# FU-AM-FU6861Q-B-002-HW-V3_0-20200620.net
KiCad netlist of a schematic drawn in Altium Designer
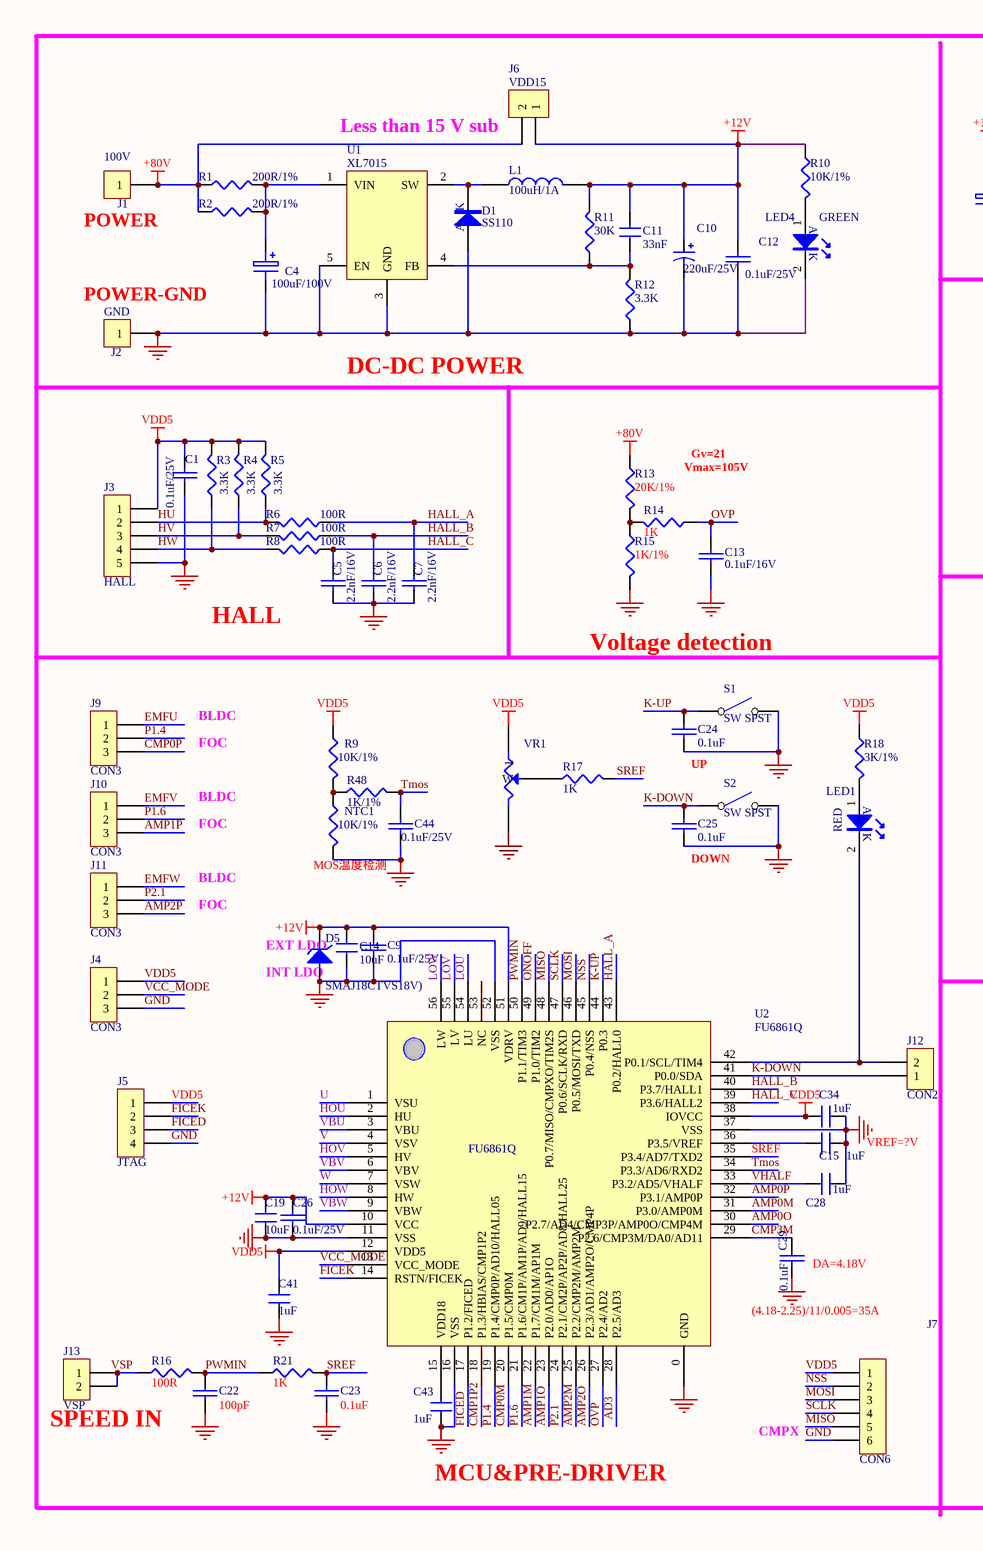
[diagram p0: FU-AM-FU6861Q-B-002-HW-V3.0-20200620.SchDoc, left]
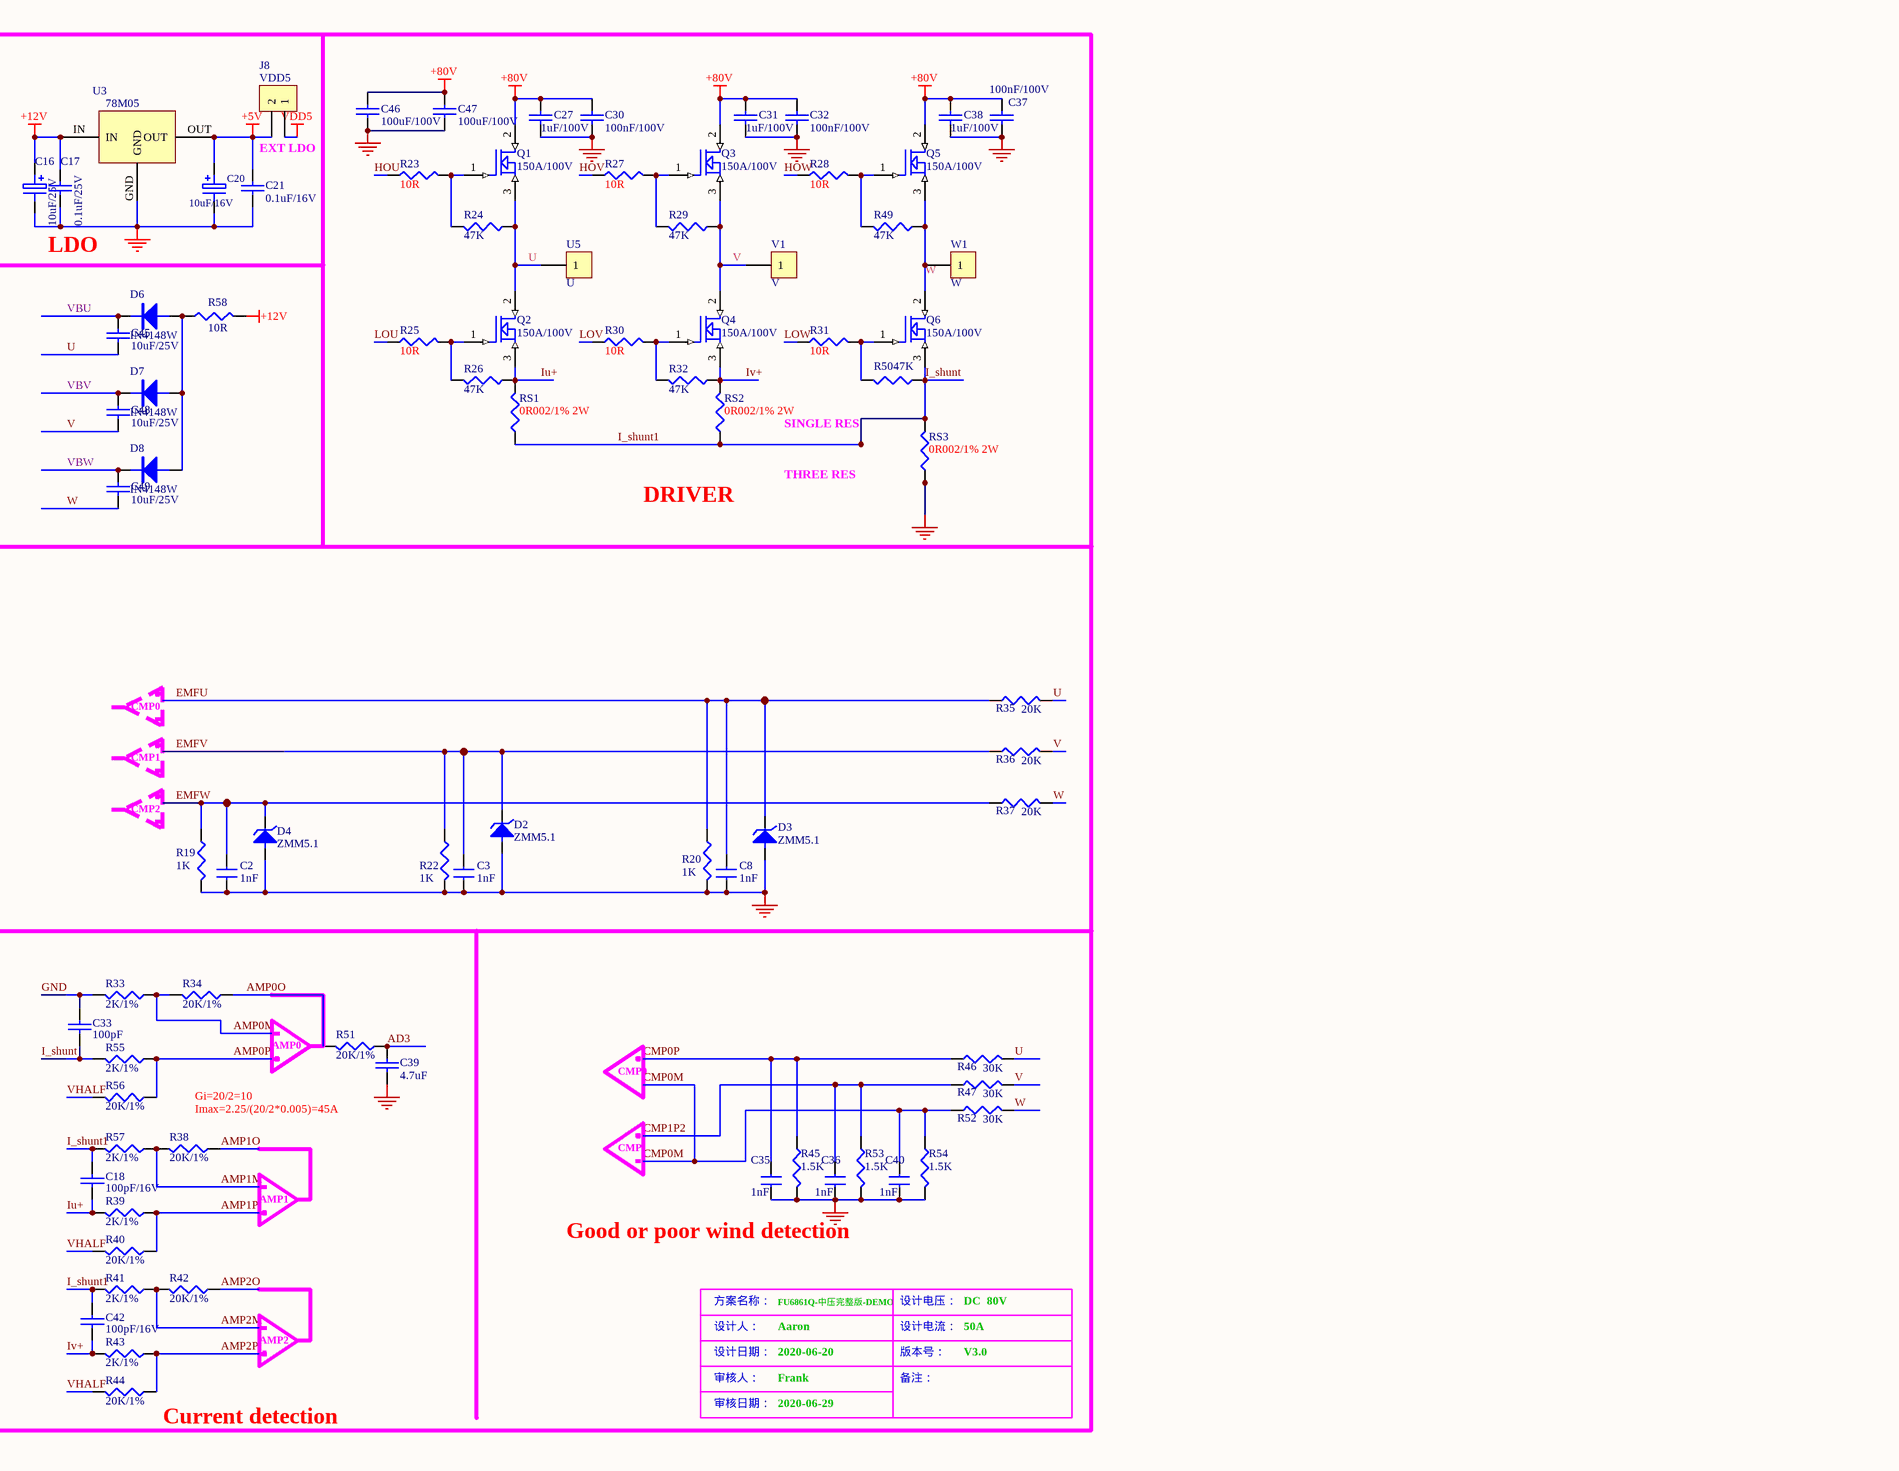
[diagram p1: FU-AM-FU6861Q-B-002-HW-V3.0-20200620.SchDoc, right]

(export (version "E")
  (design (tool "Eeschema 10.0.6"))
  (components
    (comp (ref "C1")
      (value "0.1uF/25V")
      (footprint "C0805")
      (description "Capacitor")
      (libsource (lib "") (part "CAP_1"))
    )
    (comp (ref "C2")
      (value "1nF")
      (footprint "C0805")
      (description "Capacitor")
      (libsource (lib "*") (part "CAP"))
    )
    (comp (ref "C3")
      (value "1nF")
      (footprint "C0805")
      (description "Capacitor")
      (libsource (lib "*") (part "CAP"))
    )
    (comp (ref "C4")
      (value "100uF/100V")
      (footprint "CE5-10/16")
      (description "Electrolytic Capacitor")
      (libsource (lib "*") (part "ELECTRO1"))
    )
    (comp (ref "C5")
      (value "2.2nF/16V")
      (footprint "C0805")
      (description "Capacitor")
      (libsource (lib "") (part "CAP_1"))
    )
    (comp (ref "C6")
      (value "2.2nF/16V")
      (footprint "C0805")
      (description "Capacitor")
      (libsource (lib "") (part "CAP_1"))
    )
    (comp (ref "C7")
      (value "2.2nF/16V")
      (footprint "C0805")
      (description "Capacitor")
      (libsource (lib "") (part "CAP_1"))
    )
    (comp (ref "C8")
      (value "1nF")
      (footprint "C0805")
      (description "Capacitor")
      (libsource (lib "*") (part "CAP"))
    )
    (comp (ref "C9")
      (value "0.1uF/25V")
      (footprint "C0805")
      (description "Capacitor")
      (libsource (lib "*") (part "CAP-CC"))
    )
    (comp (ref "C10")
      (value "220uF/25V")
      (footprint "CE3.5-8/12")
      (description "Polarized Capacitor (Radial)")
      (fields (field (name "PUBLISHER") "*"))
      (libsource (lib "*") (part "Cap Pol1"))
    )
    (comp (ref "C11")
      (value "33nF")
      (footprint "C0805")
      (description "Capacitor")
      (libsource (lib "*") (part "CAP"))
    )
    (comp (ref "C12")
      (value "0.1uF/25V")
      (footprint "C0805")
      (description "Capacitor")
      (libsource (lib "") (part "CAP_1"))
    )
    (comp (ref "C13")
      (value "0.1uF/16V")
      (footprint "C0805")
      (description "Capacitor")
      (libsource (lib "") (part "CAP_1"))
    )
    (comp (ref "C14")
      (value "10uF")
      (footprint "C0805")
      (description "Capacitor")
      (libsource (lib "*") (part "CAP"))
    )
    (comp (ref "C15")
      (value "1uF")
      (footprint "C0805")
      (description "Capacitor")
      (libsource (lib "*") (part "CAP"))
    )
    (comp (ref "C16")
      (value "10uF/25V")
      (footprint "C1206")
      (description "Electrolytic Capacitor")
      (libsource (lib "*") (part "ELECTRO1"))
    )
    (comp (ref "C17")
      (value "0.1uF/25V")
      (footprint "C0805")
      (description "Capacitor")
      (libsource (lib "") (part "CAP_1"))
    )
    (comp (ref "C18")
      (value "100pF/16V")
      (footprint "C0805")
      (description "Capacitor")
      (libsource (lib "") (part "CAP_1"))
    )
    (comp (ref "C19")
      (value "10uF")
      (footprint "C0805")
      (description "Capacitor")
      (libsource (lib "*") (part "CAP"))
    )
    (comp (ref "C20") (value "10uF/16V") (footprint "C1206") (libsource (lib "") (part "ELECTRO1_1")))
    (comp (ref "C21")
      (value "0.1uF/16V")
      (footprint "C0805")
      (description "Capacitor")
      (libsource (lib "*") (part "CAP-CC(SMD)"))
    )
    (comp (ref "C22")
      (value "100pF")
      (footprint "C0805")
      (description "Capacitor")
      (libsource (lib "*") (part "CAP-CC"))
    )
    (comp (ref "C23")
      (value "0.1uF")
      (footprint "C0805")
      (description "Capacitor")
      (libsource (lib "*") (part "CAP-CC"))
    )
    (comp (ref "C24")
      (value "0.1uF")
      (footprint "C0805")
      (description "Capacitor")
      (libsource (lib "") (part "CAP_1"))
    )
    (comp (ref "C25")
      (value "0.1uF")
      (footprint "C0805")
      (description "Capacitor")
      (libsource (lib "") (part "CAP_1"))
    )
    (comp (ref "C26")
      (value "0.1uF/25V")
      (footprint "C0805")
      (description "Capacitor")
      (libsource (lib "*") (part "CAP-CC"))
    )
    (comp (ref "C27")
      (value "1uF/100V")
      (footprint "C1206")
      (description "Capacitor")
      (libsource (lib "") (part "CAP_1"))
    )
    (comp (ref "C28")
      (value "1uF")
      (footprint "C0805")
      (description "Capacitor")
      (libsource (lib "*") (part "CAP"))
    )
    (comp (ref "C29")
      (value "0.1uF")
      (footprint "C0805")
      (description "Capacitor")
      (libsource (lib "") (part "CAP_1"))
    )
    (comp (ref "C30")
      (value "100nF/100V")
      (footprint "C1206")
      (description "Capacitor")
      (libsource (lib "") (part "CAP_1"))
    )
    (comp (ref "C31")
      (value "1uF/100V")
      (footprint "C1206")
      (description "Capacitor")
      (libsource (lib "") (part "CAP_1"))
    )
    (comp (ref "C32")
      (value "100nF/100V")
      (footprint "C1206")
      (description "Capacitor")
      (libsource (lib "") (part "CAP_1"))
    )
    (comp (ref "C33")
      (value "100pF")
      (footprint "C0805")
      (description "Capacitor")
      (libsource (lib "") (part "CAP_1"))
    )
    (comp (ref "C34")
      (value "1uF")
      (footprint "C0805")
      (description "Capacitor")
      (libsource (lib "*") (part "CAP"))
    )
    (comp (ref "C35")
      (value "1nF")
      (footprint "C0805")
      (description "Capacitor")
      (libsource (lib "*") (part "CAP"))
    )
    (comp (ref "C36")
      (value "1nF")
      (footprint "C0805")
      (description "Capacitor")
      (libsource (lib "*") (part "CAP"))
    )
    (comp (ref "C37")
      (value "100nF/100V")
      (footprint "C1206")
      (description "Capacitor")
      (libsource (lib "") (part "CAP_1"))
    )
    (comp (ref "C38")
      (value "1uF/100V")
      (footprint "C1206")
      (description "Capacitor")
      (libsource (lib "") (part "CAP_1"))
    )
    (comp (ref "C39")
      (value "4.7uF")
      (footprint "C0805")
      (description "Capacitor")
      (libsource (lib "") (part "CAP_1"))
    )
    (comp (ref "C40")
      (value "1nF")
      (footprint "C0805")
      (description "Capacitor")
      (libsource (lib "*") (part "CAP"))
    )
    (comp (ref "C41")
      (value "1uF")
      (footprint "C0805")
      (description "Capacitor")
      (libsource (lib "*") (part "CAP"))
    )
    (comp (ref "C42")
      (value "100pF/16V")
      (footprint "C0805")
      (description "Capacitor")
      (libsource (lib "") (part "CAP_1"))
    )
    (comp (ref "C43")
      (value "1uF")
      (footprint "C0805")
      (description "Capacitor")
      (libsource (lib "*") (part "CAP"))
    )
    (comp (ref "C44")
      (value "0.1uF/25V")
      (footprint "C0805")
      (description "Capacitor")
      (libsource (lib "*") (part "CAP-CC"))
    )
    (comp (ref "C45")
      (value "10uF/25V")
      (footprint "C0805")
      (description "Capacitor")
      (libsource (lib "*") (part "CAP-CC(SMD)"))
    )
    (comp (ref "C46")
      (value "100uF/100V")
      (footprint "CE7.5-16/25")
      (description "Capacitor")
      (libsource (lib "") (part "CAP_1"))
    )
    (comp (ref "C47")
      (value "100uF/100V")
      (footprint "CE7.5-16/25")
      (description "Capacitor")
      (libsource (lib "") (part "CAP_1"))
    )
    (comp (ref "C48")
      (value "10uF/25V")
      (footprint "C0805")
      (description "Capacitor")
      (libsource (lib "*") (part "CAP-CC(SMD)"))
    )
    (comp (ref "C49")
      (value "10uF/25V")
      (footprint "C0805")
      (description "Capacitor")
      (libsource (lib "*") (part "CAP-CC(SMD)"))
    )
    (comp (ref "D1")
      (value "SS110")
      (footprint "SMA")
      (description "Diode")
      (libsource (lib "*") (part "DIODE"))
    )
    (comp (ref "D2")
      (value "ZMM5.1")
      (footprint "SOD-123")
      (description "Zener Diode")
      (libsource (lib "*") (part "ZENER3"))
    )
    (comp (ref "D3")
      (value "ZMM5.1")
      (footprint "SOD-123")
      (description "Zener Diode")
      (libsource (lib "*") (part "ZENER3"))
    )
    (comp (ref "D4")
      (value "ZMM5.1")
      (footprint "SOD-123")
      (description "Zener Diode")
      (libsource (lib "*") (part "ZENER3"))
    )
    (comp (ref "D5")
      (value "SMAJ18CTVS18V)")
      (footprint "SMA")
      (description "Zener Diode")
      (libsource (lib "*") (part "TVS1"))
    )
    (comp (ref "D6")
      (value "IN4148W")
      (footprint "SOD-123")
      (description "Diode")
      (libsource (lib "*") (part "1N4004"))
    )
    (comp (ref "D7")
      (value "IN4148W")
      (footprint "SOD-123")
      (description "Diode")
      (libsource (lib "*") (part "1N4004"))
    )
    (comp (ref "D8")
      (value "IN4148W")
      (footprint "SOD-123")
      (description "Diode")
      (libsource (lib "*") (part "1N4004"))
    )
    (comp (ref "J1")
      (value "100V")
      (footprint "TP")
      (description "Connector")
      (libsource (lib "") (part "CON1_1"))
    )
    (comp (ref "J2")
      (value "GND")
      (footprint "TP")
      (description "Connector")
      (libsource (lib "") (part "CON1_1"))
    )
    (comp (ref "J3")
      (value "HALL")
      (footprint "XH-5P-2.54")
      (description "Connector")
      (libsource (lib "*") (part "CON5"))
    )
    (comp (ref "J4")
      (value "CON3")
      (footprint "SIP3-2.54")
      (description "Connector")
      (libsource (lib "*") (part "CON3"))
    )
    (comp (ref "J5")
      (value "JTAG")
      (footprint "SIP4-2.54")
      (description "Connector")
      (libsource (lib "*") (part "CON4"))
    )
    (comp (ref "J6")
      (value "VDD15")
      (footprint "SIP2-2.54")
      (description "Connector")
      (libsource (lib "*") (part "CON2"))
    )
    (comp (ref "J7")
      (value "CON6")
      (footprint "sip6-2.54")
      (description "Connector")
      (libsource (lib "*") (part "CON6"))
    )
    (comp (ref "J8")
      (value "VDD5")
      (footprint "SIP2-2.54")
      (description "Connector")
      (libsource (lib "*") (part "CON2"))
    )
    (comp (ref "J9")
      (value "CON3")
      (footprint "SIP3-2.54")
      (description "Connector")
      (libsource (lib "*") (part "CON3"))
    )
    (comp (ref "J10")
      (value "CON3")
      (footprint "SIP3-2.54")
      (description "Connector")
      (libsource (lib "*") (part "CON3"))
    )
    (comp (ref "J11")
      (value "CON3")
      (footprint "SIP3-2.54")
      (description "Connector")
      (libsource (lib "*") (part "CON3"))
    )
    (comp (ref "J12")
      (value "CON2")
      (footprint "SIP2-2.54")
      (description "Connector")
      (libsource (lib "SCH 常用封装") (part "CON2"))
    )
    (comp (ref "J13")
      (value "VSP")
      (footprint "SIP2-2.54")
      (description "Connector")
      (libsource (lib "") (part "CON2_1"))
    )
    (comp (ref "L1") (value "100uH/1A") (footprint "L4.5-9") (libsource (lib "*") (part "INDUCTOR")))
    (comp (ref "LED1") (value "RED") (footprint "LED0805") (libsource (lib "*") (part "LED")))
    (comp (ref "LED4") (value "GREEN") (footprint "LED0805") (libsource (lib "*") (part "LED")))
    (comp (ref "NTC1") (value "10K/1%") (footprint "R0805") (libsource (lib "*") (part "RES(SMD)")))
    (comp (ref "Q1")
      (value "150A/100V")
      (footprint "TO-220AB-W")
      (libsource (lib "*") (part "MOSFET N(GDS)"))
    )
    (comp (ref "Q2")
      (value "150A/100V")
      (footprint "TO-220AB-W")
      (libsource (lib "*") (part "MOSFET N(GDS)"))
    )
    (comp (ref "Q3")
      (value "150A/100V")
      (footprint "TO-220AB-W")
      (libsource (lib "*") (part "MOSFET N(GDS)"))
    )
    (comp (ref "Q4")
      (value "150A/100V")
      (footprint "TO-220AB-W")
      (libsource (lib "*") (part "MOSFET N(GDS)"))
    )
    (comp (ref "Q5")
      (value "150A/100V")
      (footprint "TO-220AB-W")
      (libsource (lib "*") (part "MOSFET N(GDS)"))
    )
    (comp (ref "Q6")
      (value "150A/100V")
      (footprint "TO-220AB-W")
      (libsource (lib "*") (part "MOSFET N(GDS)"))
    )
    (comp (ref "R1") (value "200R/1%") (footprint "R1206") (libsource (lib "*") (part "RES(SMD)")))
    (comp (ref "R2") (value "200R/1%") (footprint "R1206") (libsource (lib "*") (part "RES(SMD)")))
    (comp (ref "R3") (value "3.3K") (footprint "R0805") (libsource (lib "*") (part "RES(SMD)")))
    (comp (ref "R4") (value "3.3K") (footprint "R0805") (libsource (lib "*") (part "RES(SMD)")))
    (comp (ref "R5") (value "3.3K") (footprint "R0805") (libsource (lib "*") (part "RES(SMD)")))
    (comp (ref "R6") (value "100R") (footprint "R0805") (libsource (lib "*") (part "RES(SMD)")))
    (comp (ref "R7") (value "100R") (footprint "R0805") (libsource (lib "*") (part "RES(SMD)")))
    (comp (ref "R8") (value "100R") (footprint "R0805") (libsource (lib "*") (part "RES(SMD)")))
    (comp (ref "R9") (value "10K/1%") (footprint "R0805") (libsource (lib "*") (part "RES(SMD)")))
    (comp (ref "R10") (value "10K/1%") (footprint "R0805") (libsource (lib "*") (part "RES(SMD)")))
    (comp (ref "R11") (value "30K") (footprint "R0805") (libsource (lib "*") (part "RES(SMD)")))
    (comp (ref "R12") (value "3.3K") (footprint "R0805") (libsource (lib "*") (part "RES(SMD)")))
    (comp (ref "R13") (value "20K/1%") (footprint "R0805") (libsource (lib "*") (part "RES(SMD)")))
    (comp (ref "R14") (value "1K") (footprint "R0805") (libsource (lib "*") (part "RES(SMD)")))
    (comp (ref "R15") (value "1K/1%") (footprint "R0805") (libsource (lib "*") (part "RES(SMD)")))
    (comp (ref "R16") (value "100R") (footprint "R0805") (libsource (lib "*") (part "RES(SMD)")))
    (comp (ref "R17") (value "1K") (footprint "R0805") (libsource (lib "*") (part "RES(SMD)")))
    (comp (ref "R18") (value "3K/1%") (footprint "R0805") (libsource (lib "*") (part "RES(SMD)")))
    (comp (ref "R19")
      (value "1K")
      (footprint "R0805")
      (description "RES")
      (libsource (lib "*") (part "RES-SMD"))
    )
    (comp (ref "R20")
      (value "1K")
      (footprint "R0805")
      (description "RES")
      (libsource (lib "*") (part "RES-SMD"))
    )
    (comp (ref "R21") (value "1K") (footprint "R0805") (libsource (lib "*") (part "RES(SMD)")))
    (comp (ref "R22")
      (value "1K")
      (footprint "R0805")
      (description "RES")
      (libsource (lib "*") (part "RES-SMD"))
    )
    (comp (ref "R23") (value "10R") (footprint "R0805") (libsource (lib "*") (part "RES(SMD)")))
    (comp (ref "R24") (value "47K") (footprint "R0805") (libsource (lib "*") (part "RES(SMD)")))
    (comp (ref "R25") (value "10R") (footprint "R0805") (libsource (lib "*") (part "RES(SMD)")))
    (comp (ref "R26") (value "47K") (footprint "R0805") (libsource (lib "*") (part "RES(SMD)")))
    (comp (ref "R27") (value "10R") (footprint "R0805") (libsource (lib "*") (part "RES(SMD)")))
    (comp (ref "R28") (value "10R") (footprint "R0805") (libsource (lib "*") (part "RES(SMD)")))
    (comp (ref "R29") (value "47K") (footprint "R0805") (libsource (lib "*") (part "RES(SMD)")))
    (comp (ref "R30") (value "10R") (footprint "R0805") (libsource (lib "*") (part "RES(SMD)")))
    (comp (ref "R31") (value "10R") (footprint "R0805") (libsource (lib "*") (part "RES(SMD)")))
    (comp (ref "R32") (value "47K") (footprint "R0805") (libsource (lib "*") (part "RES(SMD)")))
    (comp (ref "R33") (value "2K/1%") (footprint "R0805") (libsource (lib "*") (part "RES(SMD)")))
    (comp (ref "R34") (value "20K/1%") (footprint "R0805") (libsource (lib "*") (part "RES(SMD)")))
    (comp (ref "R35")
      (value "20K")
      (footprint "R0805")
      (description "RES")
      (libsource (lib "*") (part "RES-SMD"))
    )
    (comp (ref "R36")
      (value "20K")
      (footprint "R0805")
      (description "RES")
      (libsource (lib "*") (part "RES-SMD"))
    )
    (comp (ref "R37")
      (value "20K")
      (footprint "R0805")
      (description "RES")
      (libsource (lib "*") (part "RES-SMD"))
    )
    (comp (ref "R38") (value "20K/1%") (footprint "R0805") (libsource (lib "*") (part "RES(SMD)")))
    (comp (ref "R39") (value "2K/1%") (footprint "R0805") (libsource (lib "*") (part "RES(SMD)")))
    (comp (ref "R40") (value "20K/1%") (footprint "R0805") (libsource (lib "*") (part "RES(SMD)")))
    (comp (ref "R41") (value "2K/1%") (footprint "R0805") (libsource (lib "*") (part "RES(SMD)")))
    (comp (ref "R42") (value "20K/1%") (footprint "R0805") (libsource (lib "*") (part "RES(SMD)")))
    (comp (ref "R43") (value "2K/1%") (footprint "R0805") (libsource (lib "*") (part "RES(SMD)")))
    (comp (ref "R44") (value "20K/1%") (footprint "R0805") (libsource (lib "*") (part "RES(SMD)")))
    (comp (ref "R45")
      (value "1.5K")
      (footprint "R0805")
      (description "RES")
      (libsource (lib "*") (part "RES-SMD"))
    )
    (comp (ref "R46")
      (value "30K")
      (footprint "R0805")
      (description "RES")
      (libsource (lib "*") (part "RES-SMD"))
    )
    (comp (ref "R47")
      (value "30K")
      (footprint "R0805")
      (description "RES")
      (libsource (lib "*") (part "RES-SMD"))
    )
    (comp (ref "R48") (value "1K/1%") (footprint "R0805") (libsource (lib "*") (part "RES(SMD)")))
    (comp (ref "R49") (value "47K") (footprint "R0805") (libsource (lib "*") (part "RES(SMD)")))
    (comp (ref "R50") (value "47K") (footprint "R0805") (libsource (lib "*") (part "RES(SMD)")))
    (comp (ref "R51") (value "20K/1%") (footprint "R0805") (libsource (lib "*") (part "RES(SMD)")))
    (comp (ref "R52")
      (value "30K")
      (footprint "R0805")
      (description "RES")
      (libsource (lib "*") (part "RES-SMD"))
    )
    (comp (ref "R53")
      (value "1.5K")
      (footprint "R0805")
      (description "RES")
      (libsource (lib "*") (part "RES-SMD"))
    )
    (comp (ref "R54")
      (value "1.5K")
      (footprint "R0805")
      (description "RES")
      (libsource (lib "*") (part "RES-SMD"))
    )
    (comp (ref "R55") (value "2K/1%") (footprint "R0805") (libsource (lib "*") (part "RES(SMD)")))
    (comp (ref "R56") (value "20K/1%") (footprint "R0805") (libsource (lib "*") (part "RES(SMD)")))
    (comp (ref "R57") (value "2K/1%") (footprint "R0805") (libsource (lib "*") (part "RES(SMD)")))
    (comp (ref "R58") (value "10R") (footprint "R1206") (libsource (lib "*") (part "RES(SMD)")))
    (comp (ref "RS1") (value "0R002/1% 2W") (footprint "R2512") (libsource (lib "*") (part "RES(SMD)")))
    (comp (ref "RS2") (value "0R002/1% 2W") (footprint "R2512") (libsource (lib "*") (part "RES(SMD)")))
    (comp (ref "RS3") (value "0R002/1% 2W") (footprint "R2512") (libsource (lib "*") (part "RES(SMD)")))
    (comp (ref "S1") (value "SW SPST") (footprint "SW-6/6") (libsource (lib "*") (part "SW SPST")))
    (comp (ref "S2") (value "SW SPST") (footprint "SW-6/6") (libsource (lib "*") (part "SW SPST")))
    (comp (ref "U1") (value "XL7015") (footprint "TO-252-5L") (libsource (lib "*") (part "XL7015")))
    (comp (ref "U2") (value "FU6861Q") (footprint "QFN56") (libsource (lib "*") (part "FU6861Q")))
    (comp (ref "U3") (value "78M05") (footprint "TO-252-3L") (libsource (lib "*") (part "78M05")))
    (comp (ref "U5")
      (value "U")
      (footprint "TP")
      (description "Connector")
      (libsource (lib "*") (part "CON1"))
    )
    (comp (ref "V1")
      (value "V")
      (footprint "TP")
      (description "Connector")
      (libsource (lib "*") (part "CON1"))
    )
    (comp (ref "VR1")
      (value "~")
      (footprint "VR6")
      (description "Potentiometer")
      (libsource (lib "*") (part "RV-3296"))
    )
    (comp (ref "W1")
      (value "W")
      (footprint "TP")
      (description "Connector")
      (libsource (lib "*") (part "CON1"))
    )
  )
  (nets
    (net (code "1") (name "+5V") (class "Default")
      (node (ref "C20") (pin "1") (pintype "passive"))
      (node (ref "C21") (pin "1") (pinfunction "1_1") (pintype "passive"))
      (node (ref "J8") (pin "2") (pinfunction "2_2") (pintype "passive"))
      (node (ref "U3") (pin "OUT") (pinfunction "OUT_OUT") (pintype "passive"))
    )
    (net (code "2") (name "+12V") (class "Default")
      (node (ref "C10") (pin "1") (pinfunction "1_1") (pintype "passive"))
      (node (ref "C11") (pin "1") (pinfunction "1_1") (pintype "passive"))
      (node (ref "C12") (pin "1") (pinfunction "1_1") (pintype "passive"))
      (node (ref "C14") (pin "2") (pinfunction "2_2") (pintype "passive"))
      (node (ref "C16") (pin "1") (pinfunction "1_1") (pintype "passive"))
      (node (ref "C17") (pin "1") (pinfunction "1_1") (pintype "passive"))
      (node (ref "C19") (pin "2") (pinfunction "2_2") (pintype "passive"))
      (node (ref "C26") (pin "1") (pinfunction "1_1") (pintype "passive"))
      (node (ref "C9") (pin "1") (pinfunction "1_1") (pintype "passive"))
      (node (ref "D5") (pin "2") (pinfunction "K_2") (pintype "passive"))
      (node (ref "J6") (pin "1") (pinfunction "1_1") (pintype "passive"))
      (node (ref "L1") (pin "2") (pinfunction "2_2") (pintype "passive"))
      (node (ref "R10") (pin "1") (pinfunction "1_1") (pintype "passive"))
      (node (ref "R11") (pin "2") (pinfunction "2_2") (pintype "passive"))
      (node (ref "R58") (pin "2") (pinfunction "2_2") (pintype "passive"))
      (node (ref "U2") (pin "10") (pinfunction "VCC_10") (pintype "passive"))
      (node (ref "U2") (pin "51") (pinfunction "VDRV_51") (pintype "passive"))
      (node (ref "U3") (pin "IN") (pinfunction "IN_IN") (pintype "passive"))
    )
    (net (code "3") (name "+80V") (class "Default")
      (node (ref "C27") (pin "1") (pinfunction "1_1") (pintype "passive"))
      (node (ref "C30") (pin "1") (pinfunction "1_1") (pintype "passive"))
      (node (ref "C31") (pin "1") (pinfunction "1_1") (pintype "passive"))
      (node (ref "C32") (pin "1") (pinfunction "1_1") (pintype "passive"))
      (node (ref "C37") (pin "1") (pinfunction "1_1") (pintype "passive"))
      (node (ref "C38") (pin "1") (pinfunction "1_1") (pintype "passive"))
      (node (ref "C46") (pin "1") (pinfunction "1_1") (pintype "passive"))
      (node (ref "C47") (pin "1") (pinfunction "1_1") (pintype "passive"))
      (node (ref "J1") (pin "1") (pinfunction "1_1") (pintype "passive"))
      (node (ref "J6") (pin "2") (pinfunction "2_2") (pintype "passive"))
      (node (ref "Q1") (pin "2") (pinfunction "D_2") (pintype "input"))
      (node (ref "Q3") (pin "2") (pinfunction "D_2") (pintype "input"))
      (node (ref "Q5") (pin "2") (pinfunction "D_2") (pintype "input"))
      (node (ref "R1") (pin "1") (pinfunction "1_1") (pintype "passive"))
      (node (ref "R13") (pin "1") (pinfunction "1_1") (pintype "passive"))
      (node (ref "R2") (pin "1") (pinfunction "1_1") (pintype "passive"))
    )
    (net (code "5") (name "/AD3") (class "Default")
      (node (ref "C39") (pin "1") (pinfunction "1_1") (pintype "passive"))
      (node (ref "R51") (pin "1") (pinfunction "1_1") (pintype "passive"))
      (node (ref "U2") (pin "28") (pinfunction "P2.5/AD3_28") (pintype "passive"))
    )
    (net (code "6") (name "/AMP0M") (class "Default")
      (node (ref "R33") (pin "1") (pinfunction "1_1") (pintype "passive"))
      (node (ref "R34") (pin "2") (pinfunction "2_2") (pintype "passive"))
      (node (ref "U2") (pin "31") (pinfunction "P3.0/AMP0M_31") (pintype "passive"))
    )
    (net (code "7") (name "/AMP0O") (class "Default")
      (node (ref "R34") (pin "1") (pinfunction "1_1") (pintype "passive"))
      (node (ref "R51") (pin "2") (pinfunction "2_2") (pintype "passive"))
      (node (ref "U2") (pin "30") (pinfunction "P2.7/AD4/CMP3P/AMP0O/CMP4M_30") (pintype "passive"))
    )
    (net (code "8") (name "/AMP0P") (class "Default")
      (node (ref "R55") (pin "1") (pinfunction "1_1") (pintype "passive"))
      (node (ref "R56") (pin "1") (pinfunction "1_1") (pintype "passive"))
      (node (ref "U2") (pin "32") (pinfunction "P3.1/AMP0P_32") (pintype "passive"))
    )
    (net (code "9") (name "/AMP1M") (class "Default")
      (node (ref "R38") (pin "2") (pinfunction "2_2") (pintype "passive"))
      (node (ref "R57") (pin "1") (pinfunction "1_1") (pintype "passive"))
      (node (ref "U2") (pin "22") (pinfunction "P1.7/CM1M/AP1M_22") (pintype "passive"))
    )
    (net (code "10") (name "/AMP1O") (class "Default")
      (node (ref "R38") (pin "1") (pinfunction "1_1") (pintype "passive"))
      (node (ref "U2") (pin "23") (pinfunction "P2.0/AD0/AP1O_23") (pintype "passive"))
    )
    (net (code "11") (name "/AMP1P") (class "Default")
      (node (ref "J10") (pin "3") (pinfunction "3_3") (pintype "passive"))
      (node (ref "R39") (pin "1") (pinfunction "1_1") (pintype "passive"))
      (node (ref "R40") (pin "1") (pinfunction "1_1") (pintype "passive"))
    )
    (net (code "12") (name "/AMP2M") (class "Default")
      (node (ref "R41") (pin "1") (pinfunction "1_1") (pintype "passive"))
      (node (ref "R42") (pin "2") (pinfunction "2_2") (pintype "passive"))
      (node (ref "U2") (pin "25") (pinfunction "P2.2/CMP2M/AMP2M_25") (pintype "passive"))
    )
    (net (code "13") (name "/AMP2O") (class "Default")
      (node (ref "R42") (pin "1") (pinfunction "1_1") (pintype "passive"))
      (node (ref "U2") (pin "26") (pinfunction "P2.3/AD1/AMP2O/CMP4P_26") (pintype "passive"))
    )
    (net (code "14") (name "/AMP2P") (class "Default")
      (node (ref "J11") (pin "3") (pinfunction "3_3") (pintype "passive"))
      (node (ref "R43") (pin "1") (pinfunction "1_1") (pintype "passive"))
      (node (ref "R44") (pin "1") (pinfunction "1_1") (pintype "passive"))
    )
    (net (code "15") (name "/CMP0M") (class "Default")
      (node (ref "C40") (pin "1") (pinfunction "1_1") (pintype "passive"))
      (node (ref "R52") (pin "1") (pinfunction "1_1") (pintype "passive"))
      (node (ref "R54") (pin "1") (pinfunction "1_1") (pintype "passive"))
      (node (ref "U2") (pin "20") (pinfunction "P1.5/CMP0M_20") (pintype "passive"))
    )
    (net (code "16") (name "/CMP0P") (class "Default")
      (node (ref "C35") (pin "1") (pinfunction "1_1") (pintype "passive"))
      (node (ref "J9") (pin "3") (pinfunction "3_3") (pintype "passive"))
      (node (ref "R45") (pin "1") (pinfunction "1_1") (pintype "passive"))
      (node (ref "R46") (pin "1") (pinfunction "1_1") (pintype "passive"))
    )
    (net (code "17") (name "/CMP1P2") (class "Default")
      (node (ref "C36") (pin "1") (pinfunction "1_1") (pintype "passive"))
      (node (ref "R47") (pin "1") (pinfunction "1_1") (pintype "passive"))
      (node (ref "R53") (pin "1") (pinfunction "1_1") (pintype "passive"))
      (node (ref "U2") (pin "18") (pinfunction "P1.3/HBIAS/CMP1P2_18") (pintype "passive"))
    )
    (net (code "18") (name "/CMP3M") (class "Default")
      (node (ref "C29") (pin "2") (pinfunction "2_2") (pintype "passive"))
      (node (ref "U2") (pin "29") (pinfunction "P2.6/CMP3M/DA0/AD11_29") (pintype "passive"))
    )
    (net (code "19") (name "/EMFU") (class "Default")
      (node (ref "C8") (pin "1") (pinfunction "1_1") (pintype "passive"))
      (node (ref "D3") (pin "2") (pinfunction "K_2") (pintype "passive"))
      (node (ref "J9") (pin "1") (pinfunction "1_1") (pintype "passive"))
      (node (ref "R20") (pin "1") (pinfunction "1_1") (pintype "passive"))
      (node (ref "R35") (pin "1") (pinfunction "1_1") (pintype "passive"))
    )
    (net (code "20") (name "/EMFV") (class "Default")
      (node (ref "C3") (pin "1") (pinfunction "1_1") (pintype "passive"))
      (node (ref "D2") (pin "2") (pinfunction "K_2") (pintype "passive"))
      (node (ref "J10") (pin "1") (pinfunction "1_1") (pintype "passive"))
      (node (ref "R22") (pin "1") (pinfunction "1_1") (pintype "passive"))
      (node (ref "R36") (pin "1") (pinfunction "1_1") (pintype "passive"))
    )
    (net (code "21") (name "/EMFW") (class "Default")
      (node (ref "C2") (pin "1") (pinfunction "1_1") (pintype "passive"))
      (node (ref "D4") (pin "2") (pinfunction "K_2") (pintype "passive"))
      (node (ref "J11") (pin "1") (pinfunction "1_1") (pintype "passive"))
      (node (ref "R19") (pin "1") (pinfunction "1_1") (pintype "passive"))
      (node (ref "R37") (pin "1") (pinfunction "1_1") (pintype "passive"))
    )
    (net (code "22") (name "/FICED") (class "Default")
      (node (ref "J5") (pin "3") (pinfunction "3_3") (pintype "passive"))
      (node (ref "U2") (pin "17") (pinfunction "P1.2/FICED_17") (pintype "passive"))
    )
    (net (code "23") (name "/FICEK") (class "Default")
      (node (ref "J5") (pin "2") (pinfunction "2_2") (pintype "passive"))
      (node (ref "U2") (pin "14") (pinfunction "RSTN/FICEK_14") (pintype "passive"))
    )
    (net (code "24") (name "/HALL_A") (class "Default")
      (node (ref "C7") (pin "2") (pinfunction "2_2") (pintype "passive"))
      (node (ref "R6") (pin "1") (pinfunction "1_1") (pintype "passive"))
      (node (ref "U2") (pin "43") (pinfunction "P0.2/HALL0_43") (pintype "passive"))
    )
    (net (code "25") (name "/HALL_B") (class "Default")
      (node (ref "C6") (pin "2") (pinfunction "2_2") (pintype "passive"))
      (node (ref "R7") (pin "1") (pinfunction "1_1") (pintype "passive"))
      (node (ref "U2") (pin "40") (pinfunction "P3.7/HALL1_40") (pintype "passive"))
    )
    (net (code "26") (name "/HALL_C") (class "Default")
      (node (ref "C5") (pin "2") (pinfunction "2_2") (pintype "passive"))
      (node (ref "R8") (pin "1") (pinfunction "1_1") (pintype "passive"))
      (node (ref "U2") (pin "39") (pinfunction "P3.6/HALL2_39") (pintype "passive"))
    )
    (net (code "27") (name "/HOU") (class "Default")
      (node (ref "R23") (pin "1") (pinfunction "1_1") (pintype "passive"))
      (node (ref "U2") (pin "2") (pinfunction "HU_2") (pintype "passive"))
    )
    (net (code "28") (name "/HOV") (class "Default")
      (node (ref "R27") (pin "1") (pinfunction "1_1") (pintype "passive"))
      (node (ref "U2") (pin "5") (pinfunction "HV_5") (pintype "passive"))
    )
    (net (code "29") (name "/HOW") (class "Default")
      (node (ref "R28") (pin "1") (pinfunction "1_1") (pintype "passive"))
      (node (ref "U2") (pin "8") (pinfunction "HW_8") (pintype "passive"))
    )
    (net (code "30") (name "/HU") (class "Default")
      (node (ref "J3") (pin "2") (pinfunction "2_2") (pintype "passive"))
      (node (ref "R5") (pin "1") (pinfunction "1_1") (pintype "passive"))
      (node (ref "R6") (pin "2") (pinfunction "2_2") (pintype "passive"))
    )
    (net (code "31") (name "/HV") (class "Default")
      (node (ref "J3") (pin "3") (pinfunction "3_3") (pintype "passive"))
      (node (ref "R4") (pin "1") (pinfunction "1_1") (pintype "passive"))
      (node (ref "R7") (pin "2") (pinfunction "2_2") (pintype "passive"))
    )
    (net (code "32") (name "/HW") (class "Default")
      (node (ref "J3") (pin "4") (pinfunction "4_4") (pintype "passive"))
      (node (ref "R3") (pin "1") (pinfunction "1_1") (pintype "passive"))
      (node (ref "R8") (pin "2") (pinfunction "2_2") (pintype "passive"))
    )
    (net (code "33") (name "/I_shunt") (class "Default")
      (node (ref "C18") (pin "1") (pinfunction "1_1") (pintype "passive"))
      (node (ref "C33") (pin "2") (pinfunction "2_2") (pintype "passive"))
      (node (ref "C42") (pin "1") (pinfunction "1_1") (pintype "passive"))
      (node (ref "Q6") (pin "3") (pinfunction "S_3") (pintype "input"))
      (node (ref "R41") (pin "2") (pinfunction "2_2") (pintype "passive"))
      (node (ref "R50") (pin "1") (pinfunction "1_1") (pintype "passive"))
      (node (ref "R55") (pin "2") (pinfunction "2_2") (pintype "passive"))
      (node (ref "R57") (pin "2") (pinfunction "2_2") (pintype "passive"))
      (node (ref "RS1") (pin "1") (pinfunction "1_1") (pintype "passive"))
      (node (ref "RS2") (pin "1") (pinfunction "1_1") (pintype "passive"))
      (node (ref "RS3") (pin "2") (pinfunction "2_2") (pintype "passive"))
    )
    (net (code "34") (name "/Iu+") (class "Default")
      (node (ref "C18") (pin "2") (pinfunction "2_2") (pintype "passive"))
      (node (ref "Q2") (pin "3") (pinfunction "S_3") (pintype "input"))
      (node (ref "R26") (pin "1") (pinfunction "1_1") (pintype "passive"))
      (node (ref "R39") (pin "2") (pinfunction "2_2") (pintype "passive"))
      (node (ref "RS1") (pin "2") (pinfunction "2_2") (pintype "passive"))
    )
    (net (code "35") (name "/Iv+") (class "Default")
      (node (ref "C42") (pin "2") (pinfunction "2_2") (pintype "passive"))
      (node (ref "Q4") (pin "3") (pinfunction "S_3") (pintype "input"))
      (node (ref "R32") (pin "1") (pinfunction "1_1") (pintype "passive"))
      (node (ref "R43") (pin "2") (pinfunction "2_2") (pintype "passive"))
      (node (ref "RS2") (pin "2") (pinfunction "2_2") (pintype "passive"))
    )
    (net (code "36") (name "/K-DOWN") (class "Default")
      (node (ref "C25") (pin "1") (pinfunction "1_1") (pintype "passive"))
      (node (ref "J12") (pin "1") (pinfunction "1_1") (pintype "passive"))
      (node (ref "S2") (pin "1") (pinfunction "COMMON_1") (pintype "passive"))
      (node (ref "U2") (pin "41") (pinfunction "P0.0/SDA_41") (pintype "passive"))
    )
    (net (code "37") (name "/K-UP") (class "Default")
      (node (ref "C24") (pin "1") (pinfunction "1_1") (pintype "passive"))
      (node (ref "S1") (pin "1") (pinfunction "COMMON_1") (pintype "passive"))
      (node (ref "U2") (pin "44") (pinfunction "P0.3_44") (pintype "passive"))
    )
    (net (code "38") (name "/LOU") (class "Default")
      (node (ref "R25") (pin "1") (pinfunction "1_1") (pintype "passive"))
      (node (ref "U2") (pin "54") (pinfunction "LU_54") (pintype "passive"))
    )
    (net (code "39") (name "/LOV") (class "Default")
      (node (ref "R30") (pin "1") (pinfunction "1_1") (pintype "passive"))
      (node (ref "U2") (pin "55") (pinfunction "LV_55") (pintype "passive"))
    )
    (net (code "40") (name "/LOW") (class "Default")
      (node (ref "R31") (pin "1") (pinfunction "1_1") (pintype "passive"))
      (node (ref "U2") (pin "56") (pinfunction "LW_56") (pintype "passive"))
    )
    (net (code "41") (name "/MISO") (class "Default")
      (node (ref "J7") (pin "5") (pinfunction "5_5") (pintype "passive"))
      (node (ref "U2") (pin "48") (pinfunction "P0.7/MISO/CMPXO/TIM2S_48") (pintype "passive"))
    )
    (net (code "42") (name "/MOSI") (class "Default")
      (node (ref "J7") (pin "3") (pinfunction "3_3") (pintype "passive"))
      (node (ref "U2") (pin "46") (pinfunction "P0.5/MOSI/TXD_46") (pintype "passive"))
    )
    (net (code "43") (name "/NSS") (class "Default")
      (node (ref "J7") (pin "2") (pinfunction "2_2") (pintype "passive"))
      (node (ref "U2") (pin "45") (pinfunction "P0.4/NSS_45") (pintype "passive"))
    )
    (net (code "44") (name "/ONOFF") (class "Default")
      (node (ref "U2") (pin "49") (pinfunction "P1.0/TIM2_49") (pintype "passive"))
    )
    (net (code "45") (name "/OVP") (class "Default")
      (node (ref "C13") (pin "1") (pinfunction "1_1") (pintype "passive"))
      (node (ref "R14") (pin "1") (pinfunction "1_1") (pintype "passive"))
      (node (ref "U2") (pin "27") (pinfunction "P2.4/AD2_27") (pintype "passive"))
    )
    (net (code "46") (name "/P1.4") (class "Default")
      (node (ref "J9") (pin "2") (pinfunction "2_2") (pintype "passive"))
      (node (ref "U2") (pin "19") (pinfunction "P1.4/CMP0P/AD10/HALL05_19") (pintype "passive"))
    )
    (net (code "47") (name "/P1.6") (class "Default")
      (node (ref "J10") (pin "2") (pinfunction "2_2") (pintype "passive"))
      (node (ref "U2") (pin "21") (pinfunction "P1.6/CM1P/AM1P/AD9/HALL15_21") (pintype "passive"))
    )
    (net (code "48") (name "/P2.1") (class "Default")
      (node (ref "J11") (pin "2") (pinfunction "2_2") (pintype "passive"))
      (node (ref "U2") (pin "24") (pinfunction "P2.1/CM2P/AP2P/AD8/HALL25_24") (pintype "passive"))
    )
    (net (code "49") (name "/PWMIN") (class "Default")
      (node (ref "C22") (pin "1") (pinfunction "1_1") (pintype "passive"))
      (node (ref "R16") (pin "2") (pinfunction "2_2") (pintype "passive"))
      (node (ref "R21") (pin "1") (pinfunction "1_1") (pintype "passive"))
      (node (ref "U2") (pin "50") (pinfunction "P1.1/TIM3_50") (pintype "passive"))
    )
    (net (code "50") (name "/SCLK") (class "Default")
      (node (ref "J7") (pin "4") (pinfunction "4_4") (pintype "passive"))
      (node (ref "U2") (pin "47") (pinfunction "P0.6/SCLK/RXD_47") (pintype "passive"))
    )
    (net (code "51") (name "/SREF") (class "Default")
      (node (ref "C23") (pin "1") (pinfunction "1_1") (pintype "passive"))
      (node (ref "R17") (pin "2") (pinfunction "2_2") (pintype "passive"))
      (node (ref "R21") (pin "2") (pinfunction "2_2") (pintype "passive"))
      (node (ref "U2") (pin "35") (pinfunction "P3.4/AD7/TXD2_35") (pintype "passive"))
    )
    (net (code "52") (name "/Tmos") (class "Default")
      (node (ref "C44") (pin "1") (pinfunction "1_1") (pintype "passive"))
      (node (ref "R48") (pin "2") (pinfunction "2_2") (pintype "passive"))
      (node (ref "U2") (pin "34") (pinfunction "P3.3/AD6/RXD2_34") (pintype "passive"))
    )
    (net (code "53") (name "/U") (class "Default")
      (node (ref "C45") (pin "1") (pinfunction "1_1") (pintype "passive"))
      (node (ref "Q1") (pin "3") (pinfunction "S_3") (pintype "input"))
      (node (ref "Q2") (pin "2") (pinfunction "D_2") (pintype "input"))
      (node (ref "R24") (pin "1") (pinfunction "1_1") (pintype "passive"))
      (node (ref "R35") (pin "2") (pinfunction "2_2") (pintype "passive"))
      (node (ref "R46") (pin "2") (pinfunction "2_2") (pintype "passive"))
      (node (ref "U2") (pin "1") (pinfunction "VSU_1") (pintype "passive"))
      (node (ref "U5") (pin "1") (pinfunction "1_1") (pintype "passive"))
    )
    (net (code "54") (name "/V") (class "Default")
      (node (ref "C48") (pin "1") (pinfunction "1_1") (pintype "passive"))
      (node (ref "Q3") (pin "3") (pinfunction "S_3") (pintype "input"))
      (node (ref "Q4") (pin "2") (pinfunction "D_2") (pintype "input"))
      (node (ref "R29") (pin "1") (pinfunction "1_1") (pintype "passive"))
      (node (ref "R36") (pin "2") (pinfunction "2_2") (pintype "passive"))
      (node (ref "R47") (pin "2") (pinfunction "2_2") (pintype "passive"))
      (node (ref "U2") (pin "4") (pinfunction "VSV_4") (pintype "passive"))
      (node (ref "V1") (pin "1") (pinfunction "1_1") (pintype "passive"))
    )
    (net (code "55") (name "/VBU") (class "Default")
      (node (ref "C45") (pin "2") (pinfunction "2_2") (pintype "passive"))
      (node (ref "D6") (pin "K") (pinfunction "K_K") (pintype "passive"))
      (node (ref "U2") (pin "3") (pinfunction "VBU_3") (pintype "passive"))
    )
    (net (code "56") (name "/VBV") (class "Default")
      (node (ref "C48") (pin "2") (pinfunction "2_2") (pintype "passive"))
      (node (ref "D7") (pin "K") (pinfunction "K_K") (pintype "passive"))
      (node (ref "U2") (pin "6") (pinfunction "VBV_6") (pintype "passive"))
    )
    (net (code "57") (name "/VBW") (class "Default")
      (node (ref "C49") (pin "2") (pinfunction "2_2") (pintype "passive"))
      (node (ref "D8") (pin "K") (pinfunction "K_K") (pintype "passive"))
      (node (ref "U2") (pin "9") (pinfunction "VBW_9") (pintype "passive"))
    )
    (net (code "58") (name "/VCC_MODE") (class "Default")
      (node (ref "J4") (pin "2") (pinfunction "2_2") (pintype "passive"))
      (node (ref "U2") (pin "13") (pinfunction "VCC_MODE_13") (pintype "passive"))
    )
    (net (code "59") (name "/VHALF") (class "Default")
      (node (ref "C28") (pin "1") (pinfunction "1_1") (pintype "passive"))
      (node (ref "R40") (pin "2") (pinfunction "2_2") (pintype "passive"))
      (node (ref "R44") (pin "2") (pinfunction "2_2") (pintype "passive"))
      (node (ref "R56") (pin "2") (pinfunction "2_2") (pintype "passive"))
      (node (ref "U2") (pin "33") (pinfunction "P3.2/AD5/VHALF_33") (pintype "passive"))
    )
    (net (code "61") (name "/W") (class "Default")
      (node (ref "C49") (pin "1") (pinfunction "1_1") (pintype "passive"))
      (node (ref "Q5") (pin "3") (pinfunction "S_3") (pintype "input"))
      (node (ref "Q6") (pin "2") (pinfunction "D_2") (pintype "input"))
      (node (ref "R37") (pin "2") (pinfunction "2_2") (pintype "passive"))
      (node (ref "R49") (pin "1") (pinfunction "1_1") (pintype "passive"))
      (node (ref "R52") (pin "2") (pinfunction "2_2") (pintype "passive"))
      (node (ref "U2") (pin "7") (pinfunction "VSW_7") (pintype "passive"))
      (node (ref "W1") (pin "1") (pinfunction "1_1") (pintype "passive"))
    )
    (net (code "62") (name "GND") (class "Default")
      (node (ref "C1") (pin "1") (pinfunction "1_1") (pintype "passive"))
      (node (ref "C10") (pin "2") (pinfunction "2_2") (pintype "passive"))
      (node (ref "C12") (pin "2") (pinfunction "2_2") (pintype "passive"))
      (node (ref "C13") (pin "2") (pinfunction "2_2") (pintype "passive"))
      (node (ref "C14") (pin "1") (pinfunction "1_1") (pintype "passive"))
      (node (ref "C15") (pin "2") (pinfunction "2_2") (pintype "passive"))
      (node (ref "C16") (pin "2") (pinfunction "2_2") (pintype "passive"))
      (node (ref "C17") (pin "2") (pinfunction "2_2") (pintype "passive"))
      (node (ref "C19") (pin "1") (pinfunction "1_1") (pintype "passive"))
      (node (ref "C2") (pin "2") (pinfunction "2_2") (pintype "passive"))
      (node (ref "C20") (pin "2") (pintype "passive"))
      (node (ref "C21") (pin "2") (pinfunction "2_2") (pintype "passive"))
      (node (ref "C22") (pin "2") (pinfunction "2_2") (pintype "passive"))
      (node (ref "C23") (pin "2") (pinfunction "2_2") (pintype "passive"))
      (node (ref "C24") (pin "2") (pinfunction "2_2") (pintype "passive"))
      (node (ref "C25") (pin "2") (pinfunction "2_2") (pintype "passive"))
      (node (ref "C26") (pin "2") (pinfunction "2_2") (pintype "passive"))
      (node (ref "C27") (pin "2") (pinfunction "2_2") (pintype "passive"))
      (node (ref "C28") (pin "2") (pinfunction "2_2") (pintype "passive"))
      (node (ref "C29") (pin "1") (pinfunction "1_1") (pintype "passive"))
      (node (ref "C3") (pin "2") (pinfunction "2_2") (pintype "passive"))
      (node (ref "C30") (pin "2") (pinfunction "2_2") (pintype "passive"))
      (node (ref "C31") (pin "2") (pinfunction "2_2") (pintype "passive"))
      (node (ref "C32") (pin "2") (pinfunction "2_2") (pintype "passive"))
      (node (ref "C33") (pin "1") (pinfunction "1_1") (pintype "passive"))
      (node (ref "C34") (pin "1") (pinfunction "1_1") (pintype "passive"))
      (node (ref "C35") (pin "2") (pinfunction "2_2") (pintype "passive"))
      (node (ref "C36") (pin "2") (pinfunction "2_2") (pintype "passive"))
      (node (ref "C37") (pin "2") (pinfunction "2_2") (pintype "passive"))
      (node (ref "C38") (pin "2") (pinfunction "2_2") (pintype "passive"))
      (node (ref "C39") (pin "2") (pinfunction "2_2") (pintype "passive"))
      (node (ref "C4") (pin "2") (pinfunction "2_2") (pintype "passive"))
      (node (ref "C40") (pin "2") (pinfunction "2_2") (pintype "passive"))
      (node (ref "C41") (pin "2") (pinfunction "2_2") (pintype "passive"))
      (node (ref "C43") (pin "1") (pinfunction "1_1") (pintype "passive"))
      (node (ref "C44") (pin "2") (pinfunction "2_2") (pintype "passive"))
      (node (ref "C46") (pin "2") (pinfunction "2_2") (pintype "passive"))
      (node (ref "C47") (pin "2") (pinfunction "2_2") (pintype "passive"))
      (node (ref "C5") (pin "1") (pinfunction "1_1") (pintype "passive"))
      (node (ref "C6") (pin "1") (pinfunction "1_1") (pintype "passive"))
      (node (ref "C7") (pin "1") (pinfunction "1_1") (pintype "passive"))
      (node (ref "C8") (pin "2") (pinfunction "2_2") (pintype "passive"))
      (node (ref "C9") (pin "2") (pinfunction "2_2") (pintype "passive"))
      (node (ref "D1") (pin "1") (pintype "passive"))
      (node (ref "D2") (pin "1") (pinfunction "A_1") (pintype "passive"))
      (node (ref "D3") (pin "1") (pinfunction "A_1") (pintype "passive"))
      (node (ref "D4") (pin "1") (pinfunction "A_1") (pintype "passive"))
      (node (ref "D5") (pin "1") (pinfunction "A_1") (pintype "passive"))
      (node (ref "J2") (pin "1") (pinfunction "1_1") (pintype "passive"))
      (node (ref "J3") (pin "5") (pinfunction "5_5") (pintype "passive"))
      (node (ref "J4") (pin "3") (pinfunction "3_3") (pintype "passive"))
      (node (ref "J5") (pin "4") (pinfunction "4_4") (pintype "passive"))
      (node (ref "J7") (pin "6") (pinfunction "6_6") (pintype "passive"))
      (node (ref "LED4") (pin "2") (pinfunction "2_2") (pintype "passive"))
      (node (ref "NTC1") (pin "2") (pinfunction "2_2") (pintype "passive"))
      (node (ref "R12") (pin "1") (pinfunction "1_1") (pintype "passive"))
      (node (ref "R15") (pin "2") (pinfunction "2_2") (pintype "passive"))
      (node (ref "R19") (pin "2") (pinfunction "2_2") (pintype "passive"))
      (node (ref "R20") (pin "2") (pinfunction "2_2") (pintype "passive"))
      (node (ref "R22") (pin "2") (pinfunction "2_2") (pintype "passive"))
      (node (ref "R33") (pin "2") (pinfunction "2_2") (pintype "passive"))
      (node (ref "R45") (pin "2") (pinfunction "2_2") (pintype "passive"))
      (node (ref "R53") (pin "2") (pinfunction "2_2") (pintype "passive"))
      (node (ref "R54") (pin "2") (pinfunction "2_2") (pintype "passive"))
      (node (ref "RS3") (pin "1") (pinfunction "1_1") (pintype "passive"))
      (node (ref "S1") (pin "2") (pinfunction "NO_2") (pintype "passive"))
      (node (ref "S2") (pin "2") (pinfunction "NO_2") (pintype "passive"))
      (node (ref "U1") (pin "3") (pinfunction "GND_3") (pintype "passive"))
      (node (ref "U1") (pin "5") (pinfunction "EN_5") (pintype "passive"))
      (node (ref "U2") (pin "0") (pinfunction "GND_0") (pintype "passive"))
      (node (ref "U2") (pin "11") (pinfunction "VSS_11") (pintype "passive"))
      (node (ref "U2") (pin "16") (pinfunction "VSS_16") (pintype "passive"))
      (node (ref "U2") (pin "37") (pinfunction "VSS_37") (pintype "passive"))
      (node (ref "U2") (pin "52") (pinfunction "VSS_52") (pintype "passive"))
      (node (ref "U3") (pin "GND") (pinfunction "GND_GND") (pintype "passive"))
      (node (ref "VR1") (pin "3") (pinfunction "3_3") (pintype "passive"))
    )
    (net (code "63") (name "Net-(D1-K)") (class "Default")
      (node (ref "D1") (pin "2") (pinfunction "K_2") (pintype "passive"))
      (node (ref "L1") (pin "1") (pinfunction "1_1") (pintype "passive"))
      (node (ref "U1") (pin "2") (pinfunction "SW_2") (pintype "passive"))
    )
    (net (code "64") (name "Net-(D6-PadA)") (class "Default")
      (node (ref "D6") (pin "A") (pinfunction "A_A") (pintype "passive"))
      (node (ref "D7") (pin "A") (pinfunction "A_A") (pintype "passive"))
      (node (ref "D8") (pin "A") (pinfunction "A_A") (pintype "passive"))
      (node (ref "R58") (pin "1") (pinfunction "1_1") (pintype "passive"))
    )
    (net (code "65") (name "Net-(J13-Pad1)") (class "Default")
      (node (ref "J13") (pin "1") (pinfunction "1_1") (pintype "passive"))
      (node (ref "J13") (pin "2") (pinfunction "2_2") (pintype "passive"))
      (node (ref "R16") (pin "1") (pinfunction "1_1") (pintype "passive"))
    )
    (net (code "66") (name "Net-(LED1-Pad1)") (class "Default")
      (node (ref "LED1") (pin "1") (pinfunction "1_1") (pintype "passive"))
      (node (ref "R18") (pin "2") (pinfunction "2_2") (pintype "passive"))
    )
    (net (code "67") (name "Net-(LED4-Pad1)") (class "Default")
      (node (ref "LED4") (pin "1") (pinfunction "1_1") (pintype "passive"))
      (node (ref "R10") (pin "2") (pinfunction "2_2") (pintype "passive"))
    )
    (net (code "68") (name "Net-(NTC1-Pad1)") (class "Default")
      (node (ref "NTC1") (pin "1") (pinfunction "1_1") (pintype "passive"))
      (node (ref "R48") (pin "1") (pinfunction "1_1") (pintype "passive"))
      (node (ref "R9") (pin "2") (pinfunction "2_2") (pintype "passive"))
    )
    (net (code "69") (name "Net-(Q1-G)") (class "Default")
      (node (ref "Q1") (pin "1") (pinfunction "G_1") (pintype "input"))
      (node (ref "R23") (pin "2") (pinfunction "2_2") (pintype "passive"))
      (node (ref "R24") (pin "2") (pinfunction "2_2") (pintype "passive"))
    )
    (net (code "70") (name "Net-(Q2-G)") (class "Default")
      (node (ref "Q2") (pin "1") (pinfunction "G_1") (pintype "input"))
      (node (ref "R25") (pin "2") (pinfunction "2_2") (pintype "passive"))
      (node (ref "R26") (pin "2") (pinfunction "2_2") (pintype "passive"))
    )
    (net (code "71") (name "Net-(Q3-G)") (class "Default")
      (node (ref "Q3") (pin "1") (pinfunction "G_1") (pintype "input"))
      (node (ref "R27") (pin "2") (pinfunction "2_2") (pintype "passive"))
      (node (ref "R29") (pin "2") (pinfunction "2_2") (pintype "passive"))
    )
    (net (code "72") (name "Net-(Q4-G)") (class "Default")
      (node (ref "Q4") (pin "1") (pinfunction "G_1") (pintype "input"))
      (node (ref "R30") (pin "2") (pinfunction "2_2") (pintype "passive"))
      (node (ref "R32") (pin "2") (pinfunction "2_2") (pintype "passive"))
    )
    (net (code "73") (name "Net-(Q5-G)") (class "Default")
      (node (ref "Q5") (pin "1") (pinfunction "G_1") (pintype "input"))
      (node (ref "R28") (pin "2") (pinfunction "2_2") (pintype "passive"))
      (node (ref "R49") (pin "2") (pinfunction "2_2") (pintype "passive"))
    )
    (net (code "74") (name "Net-(Q6-G)") (class "Default")
      (node (ref "Q6") (pin "1") (pinfunction "G_1") (pintype "input"))
      (node (ref "R31") (pin "2") (pinfunction "2_2") (pintype "passive"))
      (node (ref "R50") (pin "2") (pinfunction "2_2") (pintype "passive"))
    )
    (net (code "75") (name "Net-(R13-Pad2)") (class "Default")
      (node (ref "R13") (pin "2") (pinfunction "2_2") (pintype "passive"))
      (node (ref "R14") (pin "2") (pinfunction "2_2") (pintype "passive"))
      (node (ref "R15") (pin "1") (pinfunction "1_1") (pintype "passive"))
    )
    (net (code "76") (name "Net-(R17-Pad1)") (class "Default")
      (node (ref "R17") (pin "1") (pinfunction "1_1") (pintype "passive"))
      (node (ref "VR1") (pin "W") (pinfunction "W_W") (pintype "passive"))
    )
    (net (code "77") (name "Net-(U1-FB)") (class "Default")
      (node (ref "C11") (pin "2") (pinfunction "2_2") (pintype "passive"))
      (node (ref "R11") (pin "1") (pinfunction "1_1") (pintype "passive"))
      (node (ref "R12") (pin "2") (pinfunction "2_2") (pintype "passive"))
      (node (ref "U1") (pin "4") (pinfunction "FB_4") (pintype "passive"))
    )
    (net (code "78") (name "Net-(U1-VIN)") (class "Default")
      (node (ref "C4") (pin "1") (pinfunction "1_1") (pintype "passive"))
      (node (ref "R1") (pin "2") (pinfunction "2_2") (pintype "passive"))
      (node (ref "R2") (pin "2") (pinfunction "2_2") (pintype "passive"))
      (node (ref "U1") (pin "1") (pinfunction "VIN_1") (pintype "passive"))
    )
    (net (code "79") (name "Net-(U2-P0.1{slash}SCL{slash}TIM4)") (class "Default")
      (node (ref "J12") (pin "2") (pinfunction "2_2") (pintype "passive"))
      (node (ref "LED1") (pin "2") (pinfunction "2_2") (pintype "passive"))
      (node (ref "U2") (pin "42") (pinfunction "P0.1/SCL/TIM4_42") (pintype "passive"))
    )
    (net (code "80") (name "Net-(U2-P3.5{slash}VREF)") (class "Default")
      (node (ref "C15") (pin "1") (pinfunction "1_1") (pintype "passive"))
      (node (ref "U2") (pin "36") (pinfunction "P3.5/VREF_36") (pintype "passive"))
    )
    (net (code "81") (name "Net-(U2-VDD18)") (class "Default")
      (node (ref "C43") (pin "2") (pinfunction "2_2") (pintype "passive"))
      (node (ref "U2") (pin "15") (pinfunction "VDD18_15") (pintype "passive"))
    )
    (net (code "82") (name "VDD5") (class "Default")
      (node (ref "C1") (pin "2") (pinfunction "2_2") (pintype "passive"))
      (node (ref "C34") (pin "2") (pinfunction "2_2") (pintype "passive"))
      (node (ref "C41") (pin "1") (pinfunction "1_1") (pintype "passive"))
      (node (ref "J3") (pin "1") (pinfunction "1_1") (pintype "passive"))
      (node (ref "J4") (pin "1") (pinfunction "1_1") (pintype "passive"))
      (node (ref "J5") (pin "1") (pinfunction "1_1") (pintype "passive"))
      (node (ref "J7") (pin "1") (pinfunction "1_1") (pintype "passive"))
      (node (ref "J8") (pin "1") (pinfunction "1_1") (pintype "passive"))
      (node (ref "R18") (pin "1") (pinfunction "1_1") (pintype "passive"))
      (node (ref "R3") (pin "2") (pinfunction "2_2") (pintype "passive"))
      (node (ref "R4") (pin "2") (pinfunction "2_2") (pintype "passive"))
      (node (ref "R5") (pin "2") (pinfunction "2_2") (pintype "passive"))
      (node (ref "R9") (pin "1") (pinfunction "1_1") (pintype "passive"))
      (node (ref "U2") (pin "12") (pinfunction "VDD5_12") (pintype "passive"))
      (node (ref "U2") (pin "38") (pinfunction "IOVCC_38") (pintype "passive"))
      (node (ref "VR1") (pin "1") (pinfunction "1_1") (pintype "passive"))
    )
    (net (code "83") (name "unconnected-(U2-NC-Pad53)") (class "Default")
      (node (ref "U2") (pin "53") (pinfunction "NC_53") (pintype "passive"))
    )
  )
)
